# ANT.net
KiCad netlist of a schematic drawn in Altium Designer
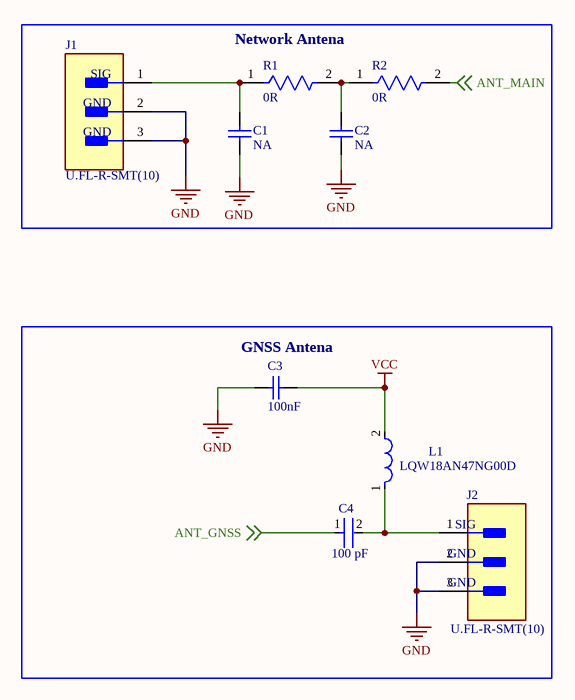
[diagram p0: ANT.SchDoc]

(export (version "E")
  (design (tool "Eeschema 10.0.6"))
  (components
    (comp (ref "C1")
      (value "NA")
      (footprint "CAPC2013X145X50ML20T25")
      (fields (field (name "PART NUMBER") "C0805C225K9PACTU") (field (name "MANUFACTURER") "Kemet"))
      (libsource (lib "Altium Content Vault") (part "CAP"))
    )
    (comp (ref "C2")
      (value "NA")
      (footprint "CAPC2013X145X50ML20T25")
      (fields (field (name "PART NUMBER") "C0805C225K9PACTU") (field (name "MANUFACTURER") "Kemet"))
      (libsource (lib "Altium Content Vault") (part "CAP"))
    )
    (comp (ref "C3")
      (value "GRM21BR71H104KA01L")
      (footprint "CAPC2013X135X45ML10T25")
      (description "Chip Capacitor, 0.1 uF, +/- 10%, 50 V, -55 to 125 degC, 0805 (2012 Metric), RoHS, Tape and Reel")
      (fields
        (field (name "VOLTAGE") "50V")
        (field (name "CAPACITANCE") "100nF")
        (field (name "TOLERANCE") "10%")
      )
      (libsource (lib "Altium Content Vault") (part "CAP-NP-2"))
    )
    (comp (ref "C4")
      (value "C0805C101J1GACTU")
      (footprint "FP-C0805C-DN-MFG")
      (description "CAP CER 100PF 100V C0G/NP0 0805")
      (fields
        (field (name "MANUFACTURER") "KEMET")
        (field (name "CAPACITANCE") "100 pF")
        (field (name "OCTOPART") "https://octopart.com/c0805c101j1gactu-kemet-123666")
      )
      (libsource (lib "Altium Content Vault") (part "b4654b650e69147ec39a6b967a45e02"))
    )
    (comp (ref "J1")
      (value "U.FL-R-SMT(10)")
      (footprint "FP-U_FL-R-SMT_10-MFG")
      (description "CONN U.FL RCPT STR 50 OHM SMD")
      (libsource (lib "Altium Content Vault") (part "eef6fde44c591823e8076210edfe12f"))
    )
    (comp (ref "J2")
      (value "U.FL-R-SMT(10)")
      (footprint "FP-U_FL-R-SMT_10-MFG")
      (description "CONN U.FL RCPT STR 50 OHM SMD")
      (libsource (lib "") (part "eef6fde44c591823e8076210edfe12f_1"))
    )
    (comp (ref "L1")
      (value "LQW18AN47NG00D")
      (footprint "FP-LQW18AN_00-MFG")
      (description "Wire Wound RF Inductor 47nH ±2% 380mA 0.29Ω 0603 (1608)")
      (fields (field (name "TOLERANCE") "2%"))
      (libsource (lib "Altium Content Vault") (part "725321dda6339637d4d059423bc1c3c"))
    )
    (comp (ref "R1")
      (value "0R")
      (footprint "FP-CRCW0805-e3-IPC_B")
      (description "RES Thick Film, 0Ω, 0.125W, 0805")
      (libsource (lib "Altium Content Vault") (part "1029c3af85768c4190bb7ad29bc67b5"))
    )
    (comp (ref "R2")
      (value "0R")
      (footprint "FP-CRCW0805-e3-IPC_B")
      (description "RES Thick Film, 0Ω, 0.125W, 0805")
      (libsource (lib "Altium Content Vault") (part "1029c3af85768c4190bb7ad29bc67b5"))
    )
  )
  (nets
    (net (code "1") (name "ANT_GNSS") (class "Default")
      (node (ref "C4") (pin "1") (pinfunction "1_1") (pintype "passive"))
    )
    (net (code "2") (name "ANT_MAIN") (class "Default")
      (node (ref "R2") (pin "2") (pinfunction "2_2") (pintype "passive"))
    )
    (net (code "3") (name "GND") (class "Default")
      (node (ref "C1") (pin "1") (pinfunction "1_1") (pintype "passive"))
      (node (ref "C2") (pin "1") (pinfunction "1_1") (pintype "passive"))
      (node (ref "C3") (pin "1") (pinfunction "1_1") (pintype "passive"))
      (node (ref "J1") (pin "2") (pinfunction "GND_2") (pintype "power_in"))
      (node (ref "J1") (pin "3") (pinfunction "GND_3") (pintype "power_in"))
      (node (ref "J2") (pin "2") (pinfunction "GND_2") (pintype "power_in"))
      (node (ref "J2") (pin "3") (pinfunction "GND_3") (pintype "power_in"))
    )
    (net (code "4") (name "Net-(C2-Pad2)") (class "Default")
      (node (ref "C2") (pin "2") (pinfunction "2_2") (pintype "passive"))
      (node (ref "R1") (pin "2") (pinfunction "2_2") (pintype "passive"))
      (node (ref "R2") (pin "1") (pinfunction "1_1") (pintype "passive"))
    )
    (net (code "5") (name "Net-(J1-SIG)") (class "Default")
      (node (ref "C1") (pin "2") (pinfunction "2_2") (pintype "passive"))
      (node (ref "J1") (pin "1") (pinfunction "SIG_1") (pintype "passive"))
      (node (ref "R1") (pin "1") (pinfunction "1_1") (pintype "passive"))
    )
    (net (code "6") (name "Net-(J2-SIG)") (class "Default")
      (node (ref "C4") (pin "2") (pinfunction "2_2") (pintype "passive"))
      (node (ref "J2") (pin "1") (pinfunction "SIG_1") (pintype "passive"))
      (node (ref "L1") (pin "1") (pinfunction "1_1") (pintype "passive"))
    )
    (net (code "7") (name "VCC") (class "Default")
      (node (ref "C3") (pin "2") (pinfunction "2_2") (pintype "passive"))
      (node (ref "L1") (pin "2") (pinfunction "2_2") (pintype "passive"))
    )
  )
)
